# osdelux_proto1_video.net
KiCad netlist of a schematic drawn in EAGLE
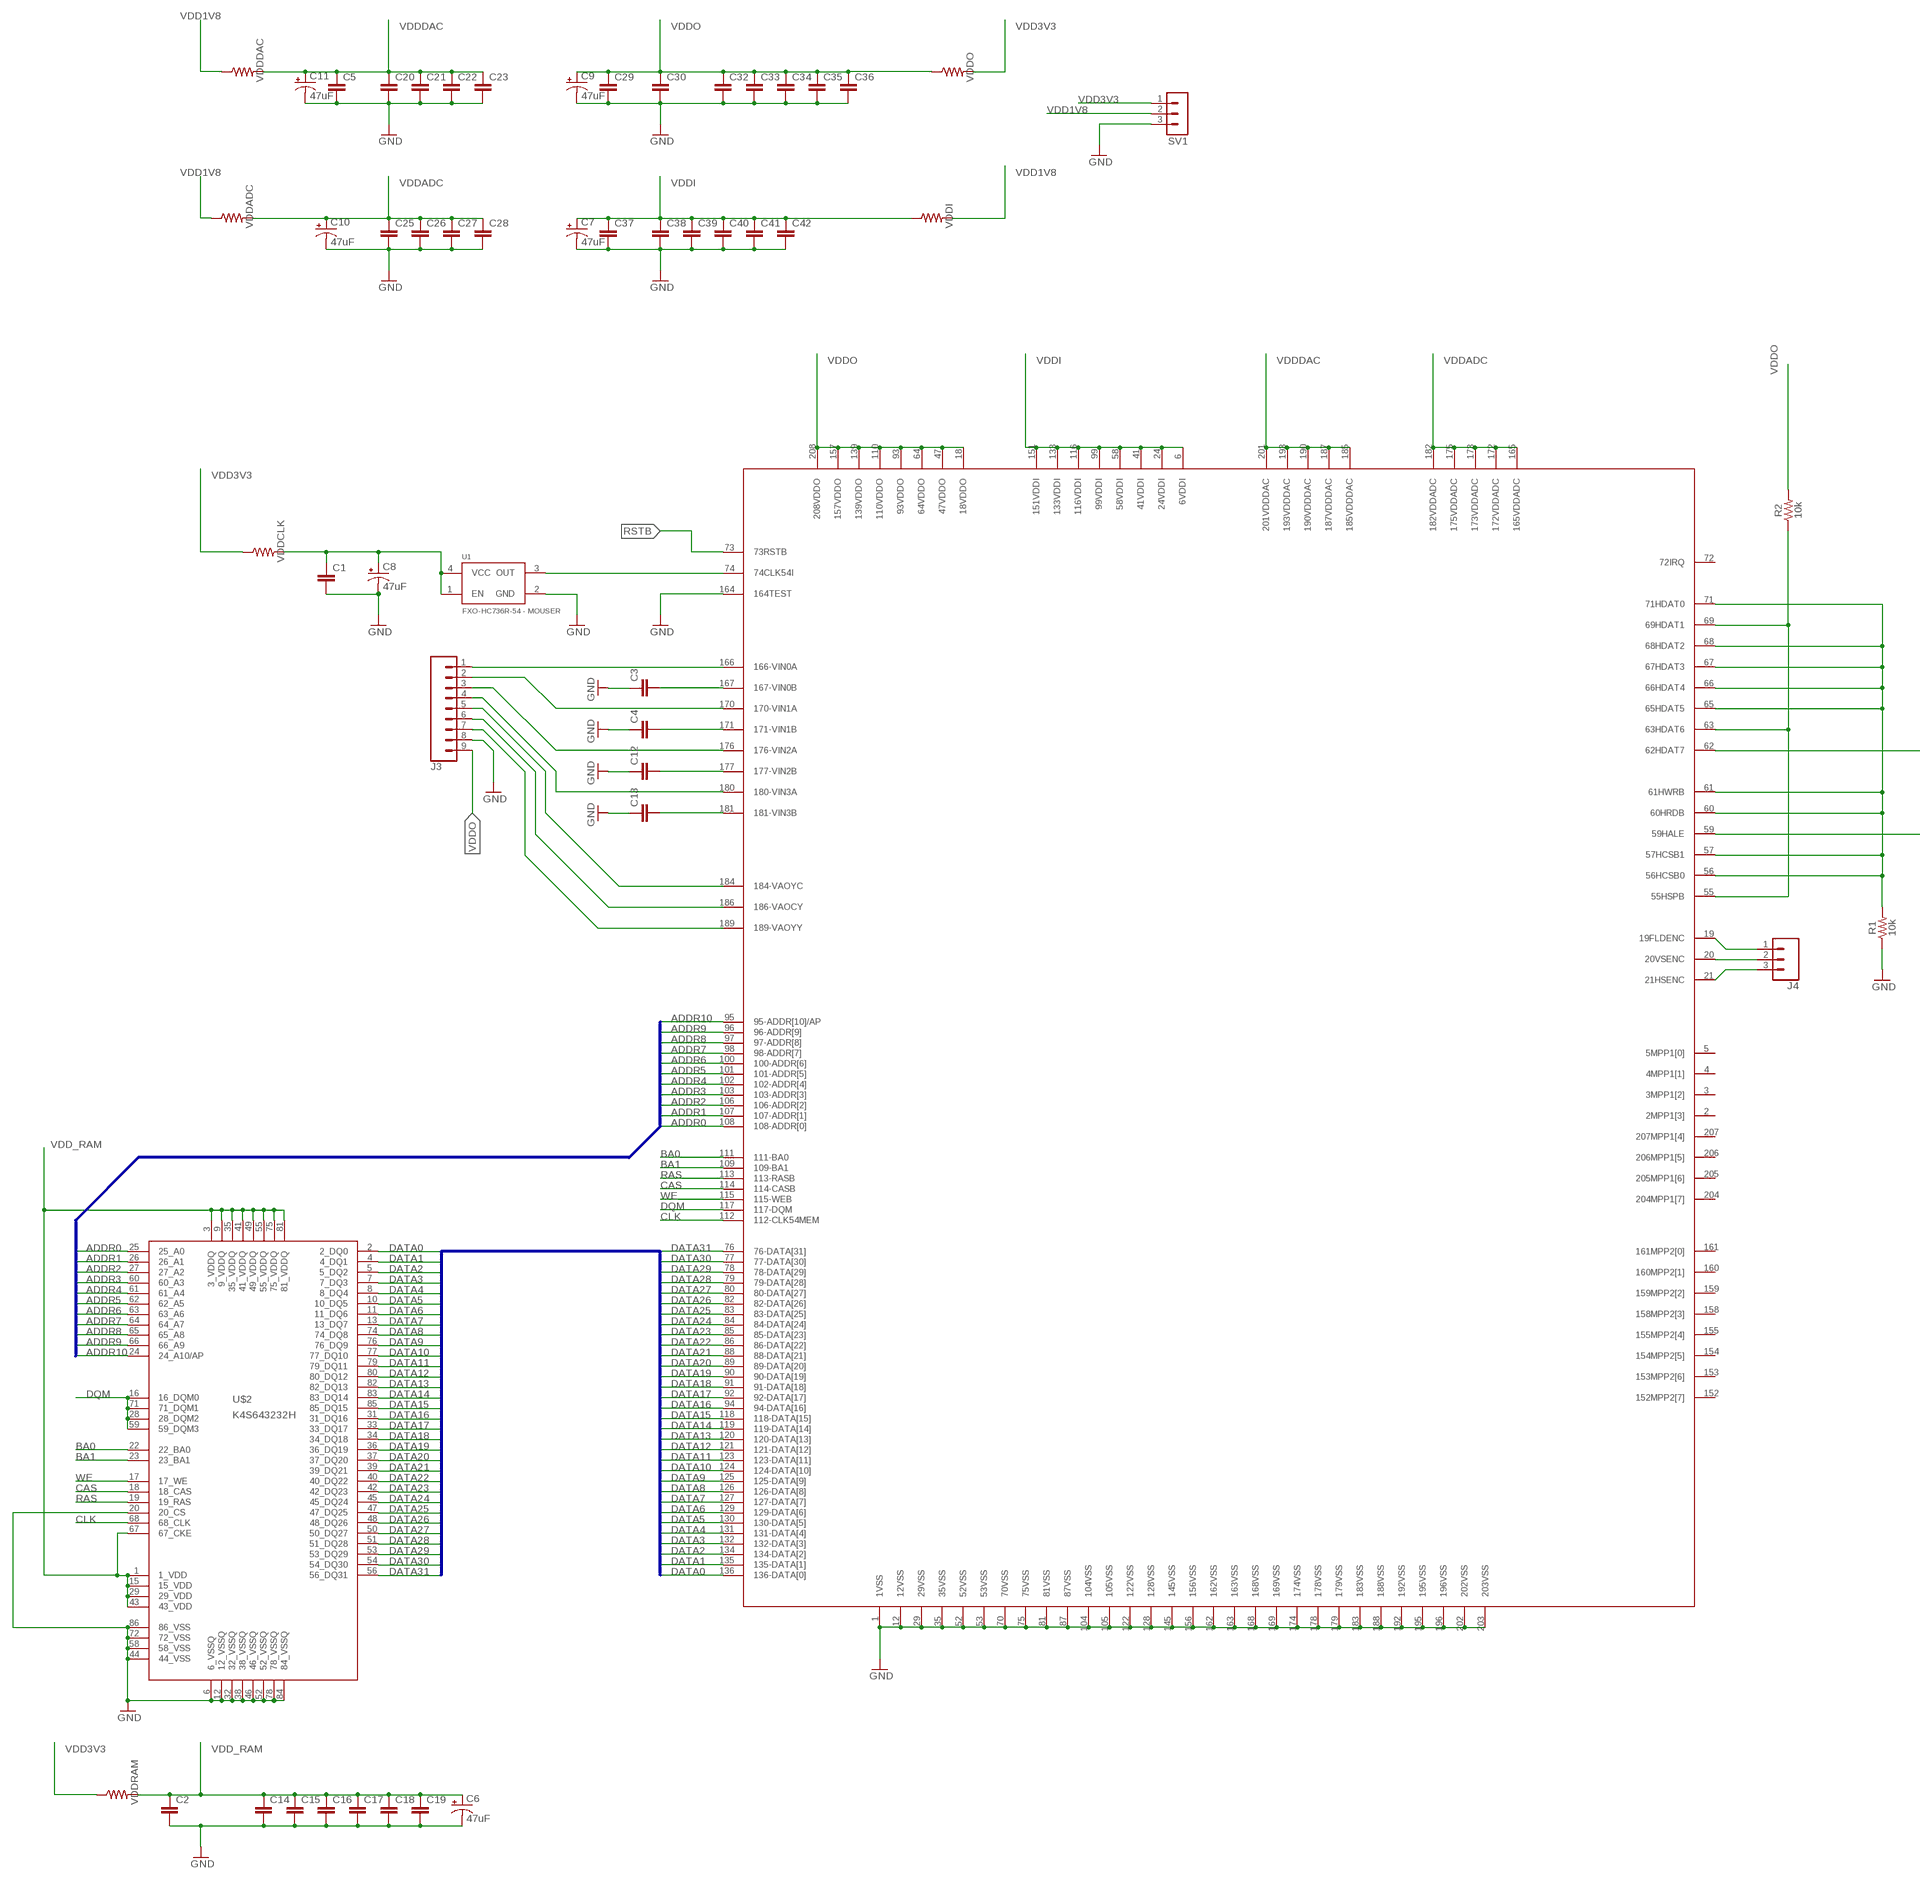
[diagram p0: schematic, sheet 1, part 1 of 2]
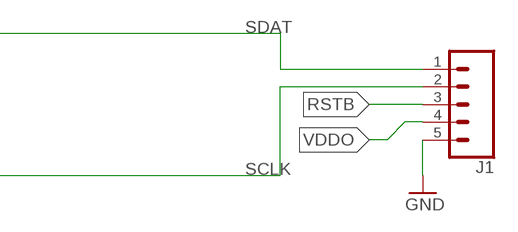
[diagram p1: schematic, sheet 1, part 2 of 2]

(export (version "E")
  (design (tool "Eeschema 10.0.6"))
  (components
    (comp (ref "C1")
      (value "CAP0805")
      (footprint "eagle-import:0805")
      (libsource (lib "eagle-import") (part "CAP0805"))
    )
    (comp (ref "C2")
      (value "CAP0805")
      (footprint "eagle-import:0805")
      (libsource (lib "eagle-import") (part "CAP0805"))
    )
    (comp (ref "C3")
      (value "CAP0805")
      (footprint "eagle-import:0805")
      (libsource (lib "eagle-import") (part "CAP0805"))
    )
    (comp (ref "C4")
      (value "CAP0805")
      (footprint "eagle-import:0805")
      (libsource (lib "eagle-import") (part "CAP0805"))
    )
    (comp (ref "C5")
      (value "CAP0805")
      (footprint "eagle-import:0805")
      (libsource (lib "eagle-import") (part "CAP0805"))
    )
    (comp (ref "C6")
      (value "47uF")
      (footprint "eagle-import:EIA3528")
      (libsource (lib "eagle-import") (part "47UF-POLAR-EIA3528-10V-10%"))
    )
    (comp (ref "C7")
      (value "47uF")
      (footprint "eagle-import:EIA3528")
      (libsource (lib "eagle-import") (part "47UF-POLAR-EIA3528-10V-10%"))
    )
    (comp (ref "C8")
      (value "47uF")
      (footprint "eagle-import:EIA3528")
      (libsource (lib "eagle-import") (part "47UF-POLAR-EIA3528-10V-10%"))
    )
    (comp (ref "C9")
      (value "47uF")
      (footprint "eagle-import:EIA3528")
      (libsource (lib "eagle-import") (part "47UF-POLAR-EIA3528-10V-10%"))
    )
    (comp (ref "C10")
      (value "47uF")
      (footprint "eagle-import:EIA3528")
      (libsource (lib "eagle-import") (part "47UF-POLAR-EIA3528-10V-10%"))
    )
    (comp (ref "C11")
      (value "47uF")
      (footprint "eagle-import:EIA3528")
      (libsource (lib "eagle-import") (part "47UF-POLAR-EIA3528-10V-10%"))
    )
    (comp (ref "C12")
      (value "CAP0805")
      (footprint "eagle-import:0805")
      (libsource (lib "eagle-import") (part "CAP0805"))
    )
    (comp (ref "C13")
      (value "CAP0805")
      (footprint "eagle-import:0805")
      (libsource (lib "eagle-import") (part "CAP0805"))
    )
    (comp (ref "C14")
      (value "CAP0805")
      (footprint "eagle-import:0805")
      (libsource (lib "eagle-import") (part "CAP0805"))
    )
    (comp (ref "C15")
      (value "CAP0805")
      (footprint "eagle-import:0805")
      (libsource (lib "eagle-import") (part "CAP0805"))
    )
    (comp (ref "C16")
      (value "CAP0805")
      (footprint "eagle-import:0805")
      (libsource (lib "eagle-import") (part "CAP0805"))
    )
    (comp (ref "C17")
      (value "CAP0805")
      (footprint "eagle-import:0805")
      (libsource (lib "eagle-import") (part "CAP0805"))
    )
    (comp (ref "C18")
      (value "CAP0805")
      (footprint "eagle-import:0805")
      (libsource (lib "eagle-import") (part "CAP0805"))
    )
    (comp (ref "C19")
      (value "CAP0805")
      (footprint "eagle-import:0805")
      (libsource (lib "eagle-import") (part "CAP0805"))
    )
    (comp (ref "C20")
      (value "CAP0805")
      (footprint "eagle-import:0805")
      (libsource (lib "eagle-import") (part "CAP0805"))
    )
    (comp (ref "C21")
      (value "CAP0805")
      (footprint "eagle-import:0805")
      (libsource (lib "eagle-import") (part "CAP0805"))
    )
    (comp (ref "C22")
      (value "CAP0805")
      (footprint "eagle-import:0805")
      (libsource (lib "eagle-import") (part "CAP0805"))
    )
    (comp (ref "C23")
      (value "CAP0805")
      (footprint "eagle-import:0805")
      (libsource (lib "eagle-import") (part "CAP0805"))
    )
    (comp (ref "C25")
      (value "CAP0805")
      (footprint "eagle-import:0805")
      (libsource (lib "eagle-import") (part "CAP0805"))
    )
    (comp (ref "C26")
      (value "CAP0805")
      (footprint "eagle-import:0805")
      (libsource (lib "eagle-import") (part "CAP0805"))
    )
    (comp (ref "C27")
      (value "CAP0805")
      (footprint "eagle-import:0805")
      (libsource (lib "eagle-import") (part "CAP0805"))
    )
    (comp (ref "C28")
      (value "CAP0805")
      (footprint "eagle-import:0805")
      (libsource (lib "eagle-import") (part "CAP0805"))
    )
    (comp (ref "C29")
      (value "CAP0805")
      (footprint "eagle-import:0805")
      (libsource (lib "eagle-import") (part "CAP0805"))
    )
    (comp (ref "C30")
      (value "CAP0805")
      (footprint "eagle-import:0805")
      (libsource (lib "eagle-import") (part "CAP0805"))
    )
    (comp (ref "C32")
      (value "CAP0805")
      (footprint "eagle-import:0805")
      (libsource (lib "eagle-import") (part "CAP0805"))
    )
    (comp (ref "C33")
      (value "CAP0805")
      (footprint "eagle-import:0805")
      (libsource (lib "eagle-import") (part "CAP0805"))
    )
    (comp (ref "C34")
      (value "CAP0805")
      (footprint "eagle-import:0805")
      (libsource (lib "eagle-import") (part "CAP0805"))
    )
    (comp (ref "C35")
      (value "CAP0805")
      (footprint "eagle-import:0805")
      (libsource (lib "eagle-import") (part "CAP0805"))
    )
    (comp (ref "C36")
      (value "CAP0805")
      (footprint "eagle-import:0805")
      (libsource (lib "eagle-import") (part "CAP0805"))
    )
    (comp (ref "C37")
      (value "CAP0805")
      (footprint "eagle-import:0805")
      (libsource (lib "eagle-import") (part "CAP0805"))
    )
    (comp (ref "C38")
      (value "CAP0805")
      (footprint "eagle-import:0805")
      (libsource (lib "eagle-import") (part "CAP0805"))
    )
    (comp (ref "C39")
      (value "CAP0805")
      (footprint "eagle-import:0805")
      (libsource (lib "eagle-import") (part "CAP0805"))
    )
    (comp (ref "C40")
      (value "CAP0805")
      (footprint "eagle-import:0805")
      (libsource (lib "eagle-import") (part "CAP0805"))
    )
    (comp (ref "C41")
      (value "CAP0805")
      (footprint "eagle-import:0805")
      (libsource (lib "eagle-import") (part "CAP0805"))
    )
    (comp (ref "C42")
      (value "CAP0805")
      (footprint "eagle-import:0805")
      (libsource (lib "eagle-import") (part "CAP0805"))
    )
    (comp (ref "J1")
      (value "CONN_05LOCK_LONGPADS")
      (footprint "eagle-import:1X05_LOCK_LONGPADS")
      (libsource (lib "eagle-import") (part "CONN_05LOCK_LONGPADS"))
    )
    (comp (ref "J3")
      (value "CONN_09LOCK-LONGPADS")
      (footprint "eagle-import:1X09_LOCK_LONGPADS")
      (libsource (lib "eagle-import") (part "CONN_09LOCK-LONGPADS"))
    )
    (comp (ref "J4")
      (value "CONN_03LOCK_LONGPADS")
      (footprint "eagle-import:1X03_LOCK_LONGPADS")
      (libsource (lib "eagle-import") (part "CONN_03LOCK_LONGPADS"))
    )
    (comp (ref "R1")
      (value "10k")
      (footprint "eagle-import:0805")
      (libsource (lib "eagle-import") (part "RESISTOR0805"))
    )
    (comp (ref "R2")
      (value "10k")
      (footprint "eagle-import:0805")
      (libsource (lib "eagle-import") (part "RESISTOR0805"))
    )
    (comp (ref "SV1")
      (value "MA03-1")
      (footprint "eagle-import:MA03-1")
      (libsource (lib "eagle-import") (part "MA03-1"))
    )
    (comp (ref "U$1")
      (value "TW2823")
      (footprint "eagle-import:LQFP208")
      (libsource (lib "eagle-import") (part "TW2823"))
    )
    (comp (ref "U$2")
      (value "K4S643232H")
      (footprint "eagle-import:TSOP86")
      (libsource (lib "eagle-import") (part "K4S643232H"))
    )
    (comp (ref "U1")
      (value "FXO-HC736R-54 - MOUSER")
      (footprint "eagle-import:CRYSTAL-SMD-7.5X5.2-6PIN")
      (libsource (lib "eagle-import") (part "OSCILLATORSMD6"))
    )
    (comp (ref "VDDADC")
      (value "RESISTOR1206")
      (footprint "eagle-import:1206")
      (libsource (lib "eagle-import") (part "RESISTOR1206"))
    )
    (comp (ref "VDDCLK")
      (value "RESISTOR1206")
      (footprint "eagle-import:1206")
      (libsource (lib "eagle-import") (part "RESISTOR1206"))
    )
    (comp (ref "VDDDAC")
      (value "RESISTOR1206")
      (footprint "eagle-import:1206")
      (libsource (lib "eagle-import") (part "RESISTOR1206"))
    )
    (comp (ref "VDDI")
      (value "RESISTOR1206")
      (footprint "eagle-import:1206")
      (libsource (lib "eagle-import") (part "RESISTOR1206"))
    )
    (comp (ref "VDDO")
      (value "RESISTOR1206")
      (footprint "eagle-import:1206")
      (libsource (lib "eagle-import") (part "RESISTOR1206"))
    )
    (comp (ref "VDDRAM")
      (value "RESISTOR1206")
      (footprint "eagle-import:1206")
      (libsource (lib "eagle-import") (part "RESISTOR1206"))
    )
  )
  (nets
    (net (code "1") (name "/72IRQ") (class "Default")
      (node (ref "U$1") (pin "72") (pinfunction "72IRQ_72") (pintype "power_in"))
    )
    (net (code "2") (name "/ADDR0") (class "Default")
      (node (ref "U$1") (pin "108") (pinfunction "108-ADDR[0]_108") (pintype "power_in"))
      (node (ref "U$2") (pin "25") (pinfunction "25_A0_25") (pintype "bidirectional"))
    )
    (net (code "3") (name "/ADDR1") (class "Default")
      (node (ref "U$1") (pin "107") (pinfunction "107-ADDR[1]_107") (pintype "power_in"))
      (node (ref "U$2") (pin "26") (pinfunction "26_A1_26") (pintype "bidirectional"))
    )
    (net (code "4") (name "/ADDR2") (class "Default")
      (node (ref "U$1") (pin "106") (pinfunction "106-ADDR[2]_106") (pintype "power_in"))
      (node (ref "U$2") (pin "27") (pinfunction "27_A2_27") (pintype "bidirectional"))
    )
    (net (code "5") (name "/ADDR3") (class "Default")
      (node (ref "U$1") (pin "103") (pinfunction "103-ADDR[3]_103") (pintype "power_in"))
      (node (ref "U$2") (pin "60") (pinfunction "60_A3_60") (pintype "bidirectional"))
    )
    (net (code "6") (name "/ADDR4") (class "Default")
      (node (ref "U$1") (pin "102") (pinfunction "102-ADDR[4]_102") (pintype "power_in"))
      (node (ref "U$2") (pin "61") (pinfunction "61_A4_61") (pintype "bidirectional"))
    )
    (net (code "7") (name "/ADDR5") (class "Default")
      (node (ref "U$1") (pin "101") (pinfunction "101-ADDR[5]_101") (pintype "power_in"))
      (node (ref "U$2") (pin "62") (pinfunction "62_A5_62") (pintype "bidirectional"))
    )
    (net (code "8") (name "/ADDR6") (class "Default")
      (node (ref "U$1") (pin "100") (pinfunction "100-ADDR[6]_100") (pintype "power_in"))
      (node (ref "U$2") (pin "63") (pinfunction "63_A6_63") (pintype "bidirectional"))
    )
    (net (code "9") (name "/ADDR7") (class "Default")
      (node (ref "U$1") (pin "98") (pinfunction "98-ADDR[7]_98") (pintype "power_in"))
      (node (ref "U$2") (pin "64") (pinfunction "64_A7_64") (pintype "bidirectional"))
    )
    (net (code "10") (name "/ADDR8") (class "Default")
      (node (ref "U$1") (pin "97") (pinfunction "97-ADDR[8]_97") (pintype "power_in"))
      (node (ref "U$2") (pin "65") (pinfunction "65_A8_65") (pintype "bidirectional"))
    )
    (net (code "11") (name "/ADDR9") (class "Default")
      (node (ref "U$1") (pin "96") (pinfunction "96-ADDR[9]_96") (pintype "power_in"))
      (node (ref "U$2") (pin "66") (pinfunction "66_A9_66") (pintype "bidirectional"))
    )
    (net (code "12") (name "/ADDR10") (class "Default")
      (node (ref "U$1") (pin "95") (pinfunction "95-ADDR[10]/AP_95") (pintype "power_in"))
      (node (ref "U$2") (pin "24") (pinfunction "24_A10/AP_24") (pintype "bidirectional"))
    )
    (net (code "13") (name "/BA0") (class "Default")
      (node (ref "U$1") (pin "111") (pinfunction "111-BA0_111") (pintype "power_in"))
      (node (ref "U$2") (pin "22") (pinfunction "22_BA0_22") (pintype "bidirectional"))
    )
    (net (code "14") (name "/BA1") (class "Default")
      (node (ref "U$1") (pin "109") (pinfunction "109-BA1_109") (pintype "power_in"))
      (node (ref "U$2") (pin "23") (pinfunction "23_BA1_23") (pintype "bidirectional"))
    )
    (net (code "15") (name "/CAS") (class "Default")
      (node (ref "U$1") (pin "114") (pinfunction "114-CASB_114") (pintype "power_in"))
      (node (ref "U$2") (pin "18") (pinfunction "18_CAS_18") (pintype "bidirectional"))
    )
    (net (code "16") (name "/CLK") (class "Default")
      (node (ref "U$1") (pin "112") (pinfunction "112-CLK54MEM_112") (pintype "power_in"))
      (node (ref "U$2") (pin "68") (pinfunction "68_CLK_68") (pintype "bidirectional"))
    )
    (net (code "17") (name "/DATA0") (class "Default")
      (node (ref "U$1") (pin "136") (pinfunction "136-DATA[0]_136") (pintype "power_in"))
      (node (ref "U$2") (pin "2") (pinfunction "2_DQ0_2") (pintype "bidirectional"))
    )
    (net (code "18") (name "/DATA1") (class "Default")
      (node (ref "U$1") (pin "135") (pinfunction "135-DATA[1]_135") (pintype "power_in"))
      (node (ref "U$2") (pin "4") (pinfunction "4_DQ1_4") (pintype "bidirectional"))
    )
    (net (code "19") (name "/DATA2") (class "Default")
      (node (ref "U$1") (pin "134") (pinfunction "134-DATA[2]_134") (pintype "power_in"))
      (node (ref "U$2") (pin "5") (pinfunction "5_DQ2_5") (pintype "bidirectional"))
    )
    (net (code "20") (name "/DATA3") (class "Default")
      (node (ref "U$1") (pin "132") (pinfunction "132-DATA[3]_132") (pintype "power_in"))
      (node (ref "U$2") (pin "7") (pinfunction "7_DQ3_7") (pintype "bidirectional"))
    )
    (net (code "21") (name "/DATA4") (class "Default")
      (node (ref "U$1") (pin "131") (pinfunction "131-DATA[4]_131") (pintype "power_in"))
      (node (ref "U$2") (pin "8") (pinfunction "8_DQ4_8") (pintype "bidirectional"))
    )
    (net (code "22") (name "/DATA5") (class "Default")
      (node (ref "U$1") (pin "130") (pinfunction "130-DATA[5]_130") (pintype "power_in"))
      (node (ref "U$2") (pin "10") (pinfunction "10_DQ5_10") (pintype "bidirectional"))
    )
    (net (code "23") (name "/DATA6") (class "Default")
      (node (ref "U$1") (pin "129") (pinfunction "129-DATA[6]_129") (pintype "power_in"))
      (node (ref "U$2") (pin "11") (pinfunction "11_DQ6_11") (pintype "bidirectional"))
    )
    (net (code "24") (name "/DATA7") (class "Default")
      (node (ref "U$1") (pin "127") (pinfunction "127-DATA[7]_127") (pintype "power_in"))
      (node (ref "U$2") (pin "13") (pinfunction "13_DQ7_13") (pintype "bidirectional"))
    )
    (net (code "25") (name "/DATA8") (class "Default")
      (node (ref "U$1") (pin "126") (pinfunction "126-DATA[8]_126") (pintype "power_in"))
      (node (ref "U$2") (pin "74") (pinfunction "74_DQ8_74") (pintype "bidirectional"))
    )
    (net (code "26") (name "/DATA9") (class "Default")
      (node (ref "U$1") (pin "125") (pinfunction "125-DATA[9]_125") (pintype "power_in"))
      (node (ref "U$2") (pin "76") (pinfunction "76_DQ9_76") (pintype "bidirectional"))
    )
    (net (code "27") (name "/DATA10") (class "Default")
      (node (ref "U$1") (pin "124") (pinfunction "124-DATA[10]_124") (pintype "power_in"))
      (node (ref "U$2") (pin "77") (pinfunction "77_DQ10_77") (pintype "bidirectional"))
    )
    (net (code "28") (name "/DATA11") (class "Default")
      (node (ref "U$1") (pin "123") (pinfunction "123-DATA[11]_123") (pintype "power_in"))
      (node (ref "U$2") (pin "79") (pinfunction "79_DQ11_79") (pintype "bidirectional"))
    )
    (net (code "29") (name "/DATA12") (class "Default")
      (node (ref "U$1") (pin "121") (pinfunction "121-DATA[12]_121") (pintype "power_in"))
      (node (ref "U$2") (pin "80") (pinfunction "80_DQ12_80") (pintype "bidirectional"))
    )
    (net (code "30") (name "/DATA13") (class "Default")
      (node (ref "U$1") (pin "120") (pinfunction "120-DATA[13]_120") (pintype "power_in"))
      (node (ref "U$2") (pin "82") (pinfunction "82_DQ13_82") (pintype "bidirectional"))
    )
    (net (code "31") (name "/DATA14") (class "Default")
      (node (ref "U$1") (pin "119") (pinfunction "119-DATA[14]_119") (pintype "power_in"))
      (node (ref "U$2") (pin "83") (pinfunction "83_DQ14_83") (pintype "bidirectional"))
    )
    (net (code "32") (name "/DATA15") (class "Default")
      (node (ref "U$1") (pin "118") (pinfunction "118-DATA[15]_118") (pintype "power_in"))
      (node (ref "U$2") (pin "85") (pinfunction "85_DQ15_85") (pintype "bidirectional"))
    )
    (net (code "33") (name "/DATA16") (class "Default")
      (node (ref "U$1") (pin "94") (pinfunction "94-DATA[16]_94") (pintype "power_in"))
      (node (ref "U$2") (pin "31") (pinfunction "31_DQ16_31") (pintype "bidirectional"))
    )
    (net (code "34") (name "/DATA17") (class "Default")
      (node (ref "U$1") (pin "92") (pinfunction "92-DATA[17]_92") (pintype "power_in"))
      (node (ref "U$2") (pin "33") (pinfunction "33_DQ17_33") (pintype "bidirectional"))
    )
    (net (code "35") (name "/DATA18") (class "Default")
      (node (ref "U$1") (pin "91") (pinfunction "91-DATA[18]_91") (pintype "power_in"))
      (node (ref "U$2") (pin "34") (pinfunction "34_DQ18_34") (pintype "bidirectional"))
    )
    (net (code "36") (name "/DATA19") (class "Default")
      (node (ref "U$1") (pin "90") (pinfunction "90-DATA[19]_90") (pintype "power_in"))
      (node (ref "U$2") (pin "36") (pinfunction "36_DQ19_36") (pintype "bidirectional"))
    )
    (net (code "37") (name "/DATA20") (class "Default")
      (node (ref "U$1") (pin "89") (pinfunction "89-DATA[20]_89") (pintype "power_in"))
      (node (ref "U$2") (pin "37") (pinfunction "37_DQ20_37") (pintype "bidirectional"))
    )
    (net (code "38") (name "/DATA21") (class "Default")
      (node (ref "U$1") (pin "88") (pinfunction "88-DATA[21]_88") (pintype "power_in"))
      (node (ref "U$2") (pin "39") (pinfunction "39_DQ21_39") (pintype "bidirectional"))
    )
    (net (code "39") (name "/DATA22") (class "Default")
      (node (ref "U$1") (pin "86") (pinfunction "86-DATA[22]_86") (pintype "power_in"))
      (node (ref "U$2") (pin "40") (pinfunction "40_DQ22_40") (pintype "bidirectional"))
    )
    (net (code "40") (name "/DATA23") (class "Default")
      (node (ref "U$1") (pin "85") (pinfunction "85-DATA[23]_85") (pintype "power_in"))
      (node (ref "U$2") (pin "42") (pinfunction "42_DQ23_42") (pintype "bidirectional"))
    )
    (net (code "41") (name "/DATA24") (class "Default")
      (node (ref "U$1") (pin "84") (pinfunction "84-DATA[24]_84") (pintype "power_in"))
      (node (ref "U$2") (pin "45") (pinfunction "45_DQ24_45") (pintype "bidirectional"))
    )
    (net (code "42") (name "/DATA25") (class "Default")
      (node (ref "U$1") (pin "83") (pinfunction "83-DATA[25]_83") (pintype "power_in"))
      (node (ref "U$2") (pin "47") (pinfunction "47_DQ25_47") (pintype "bidirectional"))
    )
    (net (code "43") (name "/DATA26") (class "Default")
      (node (ref "U$1") (pin "82") (pinfunction "82-DATA[26]_82") (pintype "power_in"))
      (node (ref "U$2") (pin "48") (pinfunction "48_DQ26_48") (pintype "bidirectional"))
    )
    (net (code "44") (name "/DATA27") (class "Default")
      (node (ref "U$1") (pin "80") (pinfunction "80-DATA[27]_80") (pintype "power_in"))
      (node (ref "U$2") (pin "50") (pinfunction "50_DQ27_50") (pintype "bidirectional"))
    )
    (net (code "45") (name "/DATA28") (class "Default")
      (node (ref "U$1") (pin "79") (pinfunction "79-DATA[28]_79") (pintype "power_in"))
      (node (ref "U$2") (pin "51") (pinfunction "51_DQ28_51") (pintype "bidirectional"))
    )
    (net (code "46") (name "/DATA29") (class "Default")
      (node (ref "U$1") (pin "78") (pinfunction "78-DATA[29]_78") (pintype "power_in"))
      (node (ref "U$2") (pin "53") (pinfunction "53_DQ29_53") (pintype "bidirectional"))
    )
    (net (code "47") (name "/DATA30") (class "Default")
      (node (ref "U$1") (pin "77") (pinfunction "77-DATA[30]_77") (pintype "power_in"))
      (node (ref "U$2") (pin "54") (pinfunction "54_DQ30_54") (pintype "bidirectional"))
    )
    (net (code "48") (name "/DATA31") (class "Default")
      (node (ref "U$1") (pin "76") (pinfunction "76-DATA[31]_76") (pintype "power_in"))
      (node (ref "U$2") (pin "56") (pinfunction "56_DQ31_56") (pintype "bidirectional"))
    )
    (net (code "49") (name "/DQM") (class "Default")
      (node (ref "U$1") (pin "117") (pinfunction "117-DQM_117") (pintype "power_in"))
      (node (ref "U$2") (pin "16") (pinfunction "16_DQM0_16") (pintype "bidirectional"))
      (node (ref "U$2") (pin "28") (pinfunction "28_DQM2_28") (pintype "bidirectional"))
      (node (ref "U$2") (pin "59") (pinfunction "59_DQM3_59") (pintype "bidirectional"))
      (node (ref "U$2") (pin "71") (pinfunction "71_DQM1_71") (pintype "bidirectional"))
    )
    (net (code "50") (name "/RAS") (class "Default")
      (node (ref "U$1") (pin "113") (pinfunction "113-RASB_113") (pintype "power_in"))
      (node (ref "U$2") (pin "19") (pinfunction "19_RAS_19") (pintype "bidirectional"))
    )
    (net (code "51") (name "/SCLK") (class "Default")
      (node (ref "J1") (pin "2") (pinfunction "2_2") (pintype "passive"))
      (node (ref "U$1") (pin "59") (pinfunction "59HALE_59") (pintype "power_in"))
    )
    (net (code "52") (name "/SDAT") (class "Default")
      (node (ref "J1") (pin "1") (pinfunction "1_1") (pintype "passive"))
      (node (ref "U$1") (pin "62") (pinfunction "62HDAT7_62") (pintype "power_in"))
    )
    (net (code "53") (name "/VDD1V8") (class "Default")
      (node (ref "SV1") (pin "2") (pinfunction "2_2") (pintype "passive"))
      (node (ref "VDDADC") (pin "1") (pinfunction "1_1") (pintype "passive"))
      (node (ref "VDDDAC") (pin "1") (pinfunction "1_1") (pintype "passive"))
      (node (ref "VDDI") (pin "2") (pinfunction "2_2") (pintype "passive"))
    )
    (net (code "54") (name "/VDD3V3") (class "Default")
      (node (ref "SV1") (pin "1") (pinfunction "1_1") (pintype "passive"))
      (node (ref "VDDCLK") (pin "1") (pinfunction "1_1") (pintype "passive"))
      (node (ref "VDDO") (pin "2") (pinfunction "2_2") (pintype "passive"))
      (node (ref "VDDRAM") (pin "1") (pinfunction "1_1") (pintype "passive"))
    )
    (net (code "55") (name "/VDDADC") (class "Default")
      (node (ref "C10") (pin "A") (pinfunction "+_A") (pintype "passive"))
      (node (ref "C25") (pin "1") (pinfunction "1_1") (pintype "passive"))
      (node (ref "C26") (pin "1") (pinfunction "1_1") (pintype "passive"))
      (node (ref "C27") (pin "1") (pinfunction "1_1") (pintype "passive"))
      (node (ref "C28") (pin "1") (pinfunction "1_1") (pintype "passive"))
      (node (ref "U$1") (pin "165") (pinfunction "165VDDADC_165") (pintype "power_in"))
      (node (ref "U$1") (pin "172") (pinfunction "172VDDADC_172") (pintype "power_in"))
      (node (ref "U$1") (pin "173") (pinfunction "173VDDADC_173") (pintype "power_in"))
      (node (ref "U$1") (pin "175") (pinfunction "175VDDADC_175") (pintype "power_in"))
      (node (ref "U$1") (pin "182") (pinfunction "182VDDADC_182") (pintype "power_in"))
      (node (ref "VDDADC") (pin "2") (pinfunction "2_2") (pintype "passive"))
    )
    (net (code "56") (name "/VDDDAC") (class "Default")
      (node (ref "C11") (pin "A") (pinfunction "+_A") (pintype "passive"))
      (node (ref "C20") (pin "1") (pinfunction "1_1") (pintype "passive"))
      (node (ref "C21") (pin "1") (pinfunction "1_1") (pintype "passive"))
      (node (ref "C22") (pin "1") (pinfunction "1_1") (pintype "passive"))
      (node (ref "C23") (pin "1") (pinfunction "1_1") (pintype "passive"))
      (node (ref "C5") (pin "1") (pinfunction "1_1") (pintype "passive"))
      (node (ref "U$1") (pin "185") (pinfunction "185VDDDAC_185") (pintype "power_in"))
      (node (ref "U$1") (pin "187") (pinfunction "187VDDDAC_187") (pintype "power_in"))
      (node (ref "U$1") (pin "190") (pinfunction "190VDDDAC_190") (pintype "power_in"))
      (node (ref "U$1") (pin "193") (pinfunction "193VDDDAC_193") (pintype "power_in"))
      (node (ref "U$1") (pin "201") (pinfunction "201VDDDAC_201") (pintype "power_in"))
      (node (ref "VDDDAC") (pin "2") (pinfunction "2_2") (pintype "passive"))
    )
    (net (code "57") (name "/VDDI") (class "Default")
      (node (ref "C37") (pin "1") (pinfunction "1_1") (pintype "passive"))
      (node (ref "C38") (pin "1") (pinfunction "1_1") (pintype "passive"))
      (node (ref "C39") (pin "1") (pinfunction "1_1") (pintype "passive"))
      (node (ref "C40") (pin "1") (pinfunction "1_1") (pintype "passive"))
      (node (ref "C41") (pin "1") (pinfunction "1_1") (pintype "passive"))
      (node (ref "C42") (pin "1") (pinfunction "1_1") (pintype "passive"))
      (node (ref "C7") (pin "A") (pinfunction "+_A") (pintype "passive"))
      (node (ref "U$1") (pin "116") (pinfunction "116VDDI_116") (pintype "power_in"))
      (node (ref "U$1") (pin "133") (pinfunction "133VDDI_133") (pintype "power_in"))
      (node (ref "U$1") (pin "151") (pinfunction "151VDDI_151") (pintype "power_in"))
      (node (ref "U$1") (pin "24") (pinfunction "24VDDI_24") (pintype "power_in"))
      (node (ref "U$1") (pin "41") (pinfunction "41VDDI_41") (pintype "power_in"))
      (node (ref "U$1") (pin "58") (pinfunction "58VDDI_58") (pintype "power_in"))
      (node (ref "U$1") (pin "6") (pinfunction "6VDDI_6") (pintype "power_in"))
      (node (ref "U$1") (pin "99") (pinfunction "99VDDI_99") (pintype "power_in"))
      (node (ref "VDDI") (pin "1") (pinfunction "1_1") (pintype "passive"))
    )
    (net (code "58") (name "/VDD_RAM") (class "Default")
      (node (ref "C14") (pin "1") (pinfunction "1_1") (pintype "passive"))
      (node (ref "C15") (pin "1") (pinfunction "1_1") (pintype "passive"))
      (node (ref "C16") (pin "1") (pinfunction "1_1") (pintype "passive"))
      (node (ref "C17") (pin "1") (pinfunction "1_1") (pintype "passive"))
      (node (ref "C18") (pin "1") (pinfunction "1_1") (pintype "passive"))
      (node (ref "C19") (pin "1") (pinfunction "1_1") (pintype "passive"))
      (node (ref "C2") (pin "1") (pinfunction "1_1") (pintype "passive"))
      (node (ref "C6") (pin "A") (pinfunction "+_A") (pintype "passive"))
      (node (ref "U$2") (pin "1") (pinfunction "1_VDD_1") (pintype "bidirectional"))
      (node (ref "U$2") (pin "15") (pinfunction "15_VDD_15") (pintype "bidirectional"))
      (node (ref "U$2") (pin "29") (pinfunction "29_VDD_29") (pintype "bidirectional"))
      (node (ref "U$2") (pin "3") (pinfunction "3_VDDQ_3") (pintype "bidirectional"))
      (node (ref "U$2") (pin "35") (pinfunction "35_VDDQ_35") (pintype "bidirectional"))
      (node (ref "U$2") (pin "41") (pinfunction "41_VDDQ_41") (pintype "bidirectional"))
      (node (ref "U$2") (pin "43") (pinfunction "43_VDD_43") (pintype "bidirectional"))
      (node (ref "U$2") (pin "49") (pinfunction "49_VDDQ_49") (pintype "bidirectional"))
      (node (ref "U$2") (pin "55") (pinfunction "55_VDDQ_55") (pintype "bidirectional"))
      (node (ref "U$2") (pin "67") (pinfunction "67_CKE_67") (pintype "bidirectional"))
      (node (ref "U$2") (pin "75") (pinfunction "75_VDDQ_75") (pintype "bidirectional"))
      (node (ref "U$2") (pin "81") (pinfunction "81_VDDQ_81") (pintype "bidirectional"))
      (node (ref "U$2") (pin "9") (pinfunction "9_VDDQ_9") (pintype "bidirectional"))
      (node (ref "VDDRAM") (pin "2") (pinfunction "2_2") (pintype "passive"))
    )
    (net (code "59") (name "/WE") (class "Default")
      (node (ref "U$1") (pin "115") (pinfunction "115-WEB_115") (pintype "power_in"))
      (node (ref "U$2") (pin "17") (pinfunction "17_WE_17") (pintype "bidirectional"))
    )
    (net (code "60") (name "GND") (class "Default")
      (node (ref "C1") (pin "2") (pinfunction "2_2") (pintype "passive"))
      (node (ref "C10") (pin "C") (pinfunction "-_C") (pintype "passive"))
      (node (ref "C11") (pin "C") (pinfunction "-_C") (pintype "passive"))
      (node (ref "C12") (pin "1") (pinfunction "1_1") (pintype "passive"))
      (node (ref "C13") (pin "1") (pinfunction "1_1") (pintype "passive"))
      (node (ref "C14") (pin "2") (pinfunction "2_2") (pintype "passive"))
      (node (ref "C15") (pin "2") (pinfunction "2_2") (pintype "passive"))
      (node (ref "C16") (pin "2") (pinfunction "2_2") (pintype "passive"))
      (node (ref "C17") (pin "2") (pinfunction "2_2") (pintype "passive"))
      (node (ref "C18") (pin "2") (pinfunction "2_2") (pintype "passive"))
      (node (ref "C19") (pin "2") (pinfunction "2_2") (pintype "passive"))
      (node (ref "C2") (pin "2") (pinfunction "2_2") (pintype "passive"))
      (node (ref "C20") (pin "2") (pinfunction "2_2") (pintype "passive"))
      (node (ref "C21") (pin "2") (pinfunction "2_2") (pintype "passive"))
      (node (ref "C22") (pin "2") (pinfunction "2_2") (pintype "passive"))
      (node (ref "C23") (pin "2") (pinfunction "2_2") (pintype "passive"))
      (node (ref "C25") (pin "2") (pinfunction "2_2") (pintype "passive"))
      (node (ref "C26") (pin "2") (pinfunction "2_2") (pintype "passive"))
      (node (ref "C27") (pin "2") (pinfunction "2_2") (pintype "passive"))
      (node (ref "C28") (pin "2") (pinfunction "2_2") (pintype "passive"))
      (node (ref "C29") (pin "2") (pinfunction "2_2") (pintype "passive"))
      (node (ref "C3") (pin "1") (pinfunction "1_1") (pintype "passive"))
      (node (ref "C30") (pin "2") (pinfunction "2_2") (pintype "passive"))
      (node (ref "C32") (pin "2") (pinfunction "2_2") (pintype "passive"))
      (node (ref "C33") (pin "2") (pinfunction "2_2") (pintype "passive"))
      (node (ref "C34") (pin "2") (pinfunction "2_2") (pintype "passive"))
      (node (ref "C35") (pin "2") (pinfunction "2_2") (pintype "passive"))
      (node (ref "C36") (pin "2") (pinfunction "2_2") (pintype "passive"))
      (node (ref "C37") (pin "2") (pinfunction "2_2") (pintype "passive"))
      (node (ref "C38") (pin "2") (pinfunction "2_2") (pintype "passive"))
      (node (ref "C39") (pin "2") (pinfunction "2_2") (pintype "passive"))
      (node (ref "C4") (pin "1") (pinfunction "1_1") (pintype "passive"))
      (node (ref "C40") (pin "2") (pinfunction "2_2") (pintype "passive"))
      (node (ref "C41") (pin "2") (pinfunction "2_2") (pintype "passive"))
      (node (ref "C42") (pin "2") (pinfunction "2_2") (pintype "passive"))
      (node (ref "C5") (pin "2") (pinfunction "2_2") (pintype "passive"))
      (node (ref "C6") (pin "C") (pinfunction "-_C") (pintype "passive"))
      (node (ref "C7") (pin "C") (pinfunction "-_C") (pintype "passive"))
      (node (ref "C8") (pin "C") (pinfunction "-_C") (pintype "passive"))
      (node (ref "C9") (pin "C") (pinfunction "-_C") (pintype "passive"))
      (node (ref "J1") (pin "5") (pinfunction "5_5") (pintype "passive"))
      (node (ref "J3") (pin "8") (pinfunction "8_8") (pintype "passive"))
      (node (ref "R1") (pin "1") (pinfunction "1_1") (pintype "passive"))
      (node (ref "SV1") (pin "3") (pinfunction "3_3") (pintype "passive"))
      (node (ref "U$1") (pin "1") (pinfunction "1VSS_1") (pintype "power_in"))
      (node (ref "U$1") (pin "104") (pinfunction "104VSS_104") (pintype "power_in"))
      (node (ref "U$1") (pin "105") (pinfunction "105VSS_105") (pintype "power_in"))
      (node (ref "U$1") (pin "12") (pinfunction "12VSS_12") (pintype "power_in"))
      (node (ref "U$1") (pin "122") (pinfunction "122VSS_122") (pintype "power_in"))
      (node (ref "U$1") (pin "128") (pinfunction "128VSS_128") (pintype "power_in"))
      (node (ref "U$1") (pin "145") (pinfunction "145VSS_145") (pintype "power_in"))
      (node (ref "U$1") (pin "156") (pinfunction "156VSS_156") (pintype "power_in"))
      (node (ref "U$1") (pin "162") (pinfunction "162VSS_162") (pintype "power_in"))
      (node (ref "U$1") (pin "163") (pinfunction "163VSS_163") (pintype "power_in"))
      (node (ref "U$1") (pin "164") (pinfunction "164TEST_164") (pintype "power_in"))
      (node (ref "U$1") (pin "168") (pinfunction "168VSS_168") (pintype "power_in"))
      (node (ref "U$1") (pin "169") (pinfunction "169VSS_169") (pintype "power_in"))
      (node (ref "U$1") (pin "174") (pinfunction "174VSS_174") (pintype "power_in"))
      (node (ref "U$1") (pin "178") (pinfunction "178VSS_178") (pintype "power_in"))
      (node (ref "U$1") (pin "179") (pinfunction "179VSS_179") (pintype "power_in"))
      (node (ref "U$1") (pin "183") (pinfunction "183VSS_183") (pintype "power_in"))
      (node (ref "U$1") (pin "188") (pinfunction "188VSS_188") (pintype "power_in"))
      (node (ref "U$1") (pin "192") (pinfunction "192VSS_192") (pintype "power_in"))
      (node (ref "U$1") (pin "195") (pinfunction "195VSS_195") (pintype "power_in"))
      (node (ref "U$1") (pin "196") (pinfunction "196VSS_196") (pintype "power_in"))
      (node (ref "U$1") (pin "202") (pinfunction "202VSS_202") (pintype "power_in"))
      (node (ref "U$1") (pin "203") (pinfunction "203VSS_203") (pintype "power_in"))
      (node (ref "U$1") (pin "29") (pinfunction "29VSS_29") (pintype "power_in"))
      (node (ref "U$1") (pin "35") (pinfunction "35VSS_35") (pintype "power_in"))
      (node (ref "U$1") (pin "52") (pinfunction "52VSS_52") (pintype "power_in"))
      (node (ref "U$1") (pin "53") (pinfunction "53VSS_53") (pintype "power_in"))
      (node (ref "U$1") (pin "70") (pinfunction "70VSS_70") (pintype "power_in"))
      (node (ref "U$1") (pin "75") (pinfunction "75VSS_75") (pintype "power_in"))
      (node (ref "U$1") (pin "81") (pinfunction "81VSS_81") (pintype "power_in"))
      (node (ref "U$1") (pin "87") (pinfunction "87VSS_87") (pintype "power_in"))
      (node (ref "U$2") (pin "12") (pinfunction "12_VSSQ_12") (pintype "bidirectional"))
      (node (ref "U$2") (pin "20") (pinfunction "20_CS_20") (pintype "bidirectional"))
      (node (ref "U$2") (pin "32") (pinfunction "32_VSSQ_32") (pintype "bidirectional"))
      (node (ref "U$2") (pin "38") (pinfunction "38_VSSQ_38") (pintype "bidirectional"))
      (node (ref "U$2") (pin "44") (pinfunction "44_VSS_44") (pintype "bidirectional"))
      (node (ref "U$2") (pin "46") (pinfunction "46_VSSQ_46") (pintype "bidirectional"))
      (node (ref "U$2") (pin "52") (pinfunction "52_VSSQ_52") (pintype "bidirectional"))
      (node (ref "U$2") (pin "58") (pinfunction "58_VSS_58") (pintype "bidirectional"))
      (node (ref "U$2") (pin "6") (pinfunction "6_VSSQ_6") (pintype "bidirectional"))
      (node (ref "U$2") (pin "72") (pinfunction "72_VSS_72") (pintype "bidirectional"))
      (node (ref "U$2") (pin "78") (pinfunction "78_VSSQ_78") (pintype "bidirectional"))
      (node (ref "U$2") (pin "84") (pinfunction "84_VSSQ_84") (pintype "bidirectional"))
      (node (ref "U$2") (pin "86") (pinfunction "86_VSS_86") (pintype "bidirectional"))
      (node (ref "U1") (pin "2") (pinfunction "GND_2") (pintype "bidirectional"))
    )
    (net (code "61") (name "Net-(C8-+)") (class "Default")
      (node (ref "C1") (pin "1") (pinfunction "1_1") (pintype "passive"))
      (node (ref "C8") (pin "A") (pinfunction "+_A") (pintype "passive"))
      (node (ref "U1") (pin "1") (pinfunction "EN_1") (pintype "bidirectional"))
      (node (ref "U1") (pin "4") (pinfunction "VCC_4") (pintype "bidirectional"))
      (node (ref "VDDCLK") (pin "2") (pinfunction "2_2") (pintype "passive"))
    )
    (net (code "62") (name "Net-(U$1-19FLDENC)") (class "Default")
      (node (ref "J4") (pin "1") (pinfunction "1_1") (pintype "passive"))
      (node (ref "U$1") (pin "19") (pinfunction "19FLDENC_19") (pintype "bidirectional"))
    )
    (net (code "63") (name "Net-(U$1-20VSENC)") (class "Default")
      (node (ref "J4") (pin "2") (pinfunction "2_2") (pintype "passive"))
      (node (ref "U$1") (pin "20") (pinfunction "20VSENC_20") (pintype "bidirectional"))
    )
    (net (code "64") (name "Net-(U$1-21HSENC)") (class "Default")
      (node (ref "J4") (pin "3") (pinfunction "3_3") (pintype "passive"))
      (node (ref "U$1") (pin "21") (pinfunction "21HSENC_21") (pintype "bidirectional"))
    )
    (net (code "65") (name "Net-(U$1-55HSPB)") (class "Default")
      (node (ref "R2") (pin "1") (pinfunction "1_1") (pintype "passive"))
      (node (ref "U$1") (pin "55") (pinfunction "55HSPB_55") (pintype "power_in"))
      (node (ref "U$1") (pin "63") (pinfunction "63HDAT6_63") (pintype "power_in"))
      (node (ref "U$1") (pin "69") (pinfunction "69HDAT1_69") (pintype "power_in"))
    )
    (net (code "66") (name "Net-(U$1-56HCSB0)") (class "Default")
      (node (ref "R1") (pin "2") (pinfunction "2_2") (pintype "passive"))
      (node (ref "U$1") (pin "56") (pinfunction "56HCSB0_56") (pintype "power_in"))
      (node (ref "U$1") (pin "57") (pinfunction "57HCSB1_57") (pintype "power_in"))
      (node (ref "U$1") (pin "60") (pinfunction "60HRDB_60") (pintype "power_in"))
      (node (ref "U$1") (pin "61") (pinfunction "61HWRB_61") (pintype "power_in"))
      (node (ref "U$1") (pin "65") (pinfunction "65HDAT5_65") (pintype "power_in"))
      (node (ref "U$1") (pin "66") (pinfunction "66HDAT4_66") (pintype "power_in"))
      (node (ref "U$1") (pin "67") (pinfunction "67HDAT3_67") (pintype "power_in"))
      (node (ref "U$1") (pin "68") (pinfunction "68HDAT2_68") (pintype "power_in"))
      (node (ref "U$1") (pin "71") (pinfunction "71HDAT0_71") (pintype "power_in"))
    )
    (net (code "67") (name "Net-(U$1-74CLK54I)") (class "Default")
      (node (ref "U$1") (pin "74") (pinfunction "74CLK54I_74") (pintype "power_in"))
      (node (ref "U1") (pin "3") (pinfunction "OUT_3") (pintype "bidirectional"))
    )
    (net (code "68") (name "Net-(U$1-166-VIN0A)") (class "Default")
      (node (ref "J3") (pin "1") (pinfunction "1_1") (pintype "passive"))
      (node (ref "U$1") (pin "166") (pinfunction "166-VIN0A_166") (pintype "power_in"))
    )
    (net (code "69") (name "Net-(U$1-167-VIN0B)") (class "Default")
      (node (ref "C3") (pin "2") (pinfunction "2_2") (pintype "passive"))
      (node (ref "U$1") (pin "167") (pinfunction "167-VIN0B_167") (pintype "power_in"))
    )
    (net (code "70") (name "Net-(U$1-170-VIN1A)") (class "Default")
      (node (ref "J3") (pin "2") (pinfunction "2_2") (pintype "passive"))
      (node (ref "U$1") (pin "170") (pinfunction "170-VIN1A_170") (pintype "power_in"))
    )
    (net (code "71") (name "Net-(U$1-171-VIN1B)") (class "Default")
      (node (ref "C4") (pin "2") (pinfunction "2_2") (pintype "passive"))
      (node (ref "U$1") (pin "171") (pinfunction "171-VIN1B_171") (pintype "power_in"))
    )
    (net (code "72") (name "Net-(U$1-176-VIN2A)") (class "Default")
      (node (ref "J3") (pin "3") (pinfunction "3_3") (pintype "passive"))
      (node (ref "U$1") (pin "176") (pinfunction "176-VIN2A_176") (pintype "power_in"))
    )
    (net (code "73") (name "Net-(U$1-177-VIN2B)") (class "Default")
      (node (ref "C12") (pin "2") (pinfunction "2_2") (pintype "passive"))
      (node (ref "U$1") (pin "177") (pinfunction "177-VIN2B_177") (pintype "power_in"))
    )
    (net (code "74") (name "Net-(U$1-180-VIN3A)") (class "Default")
      (node (ref "J3") (pin "4") (pinfunction "4_4") (pintype "passive"))
      (node (ref "U$1") (pin "180") (pinfunction "180-VIN3A_180") (pintype "power_in"))
    )
    (net (code "75") (name "Net-(U$1-181-VIN3B)") (class "Default")
      (node (ref "C13") (pin "2") (pinfunction "2_2") (pintype "passive"))
      (node (ref "U$1") (pin "181") (pinfunction "181-VIN3B_181") (pintype "power_in"))
    )
    (net (code "76") (name "Net-(U$1-184-VAOYC)") (class "Default")
      (node (ref "J3") (pin "5") (pinfunction "5_5") (pintype "passive"))
      (node (ref "U$1") (pin "184") (pinfunction "184-VAOYC_184") (pintype "power_in"))
    )
    (net (code "77") (name "Net-(U$1-186-VAOCY)") (class "Default")
      (node (ref "J3") (pin "6") (pinfunction "6_6") (pintype "passive"))
      (node (ref "U$1") (pin "186") (pinfunction "186-VAOCY_186") (pintype "power_in"))
    )
    (net (code "78") (name "Net-(U$1-189-VAOYY)") (class "Default")
      (node (ref "J3") (pin "7") (pinfunction "7_7") (pintype "passive"))
      (node (ref "U$1") (pin "189") (pinfunction "189-VAOYY_189") (pintype "power_in"))
    )
    (net (code "79") (name "RSTB") (class "Default")
      (node (ref "J1") (pin "3") (pinfunction "3_3") (pintype "passive"))
      (node (ref "U$1") (pin "73") (pinfunction "73RSTB_73") (pintype "power_in"))
    )
    (net (code "80") (name "VDDO") (class "Default")
      (node (ref "C29") (pin "1") (pinfunction "1_1") (pintype "passive"))
      (node (ref "C30") (pin "1") (pinfunction "1_1") (pintype "passive"))
      (node (ref "C32") (pin "1") (pinfunction "1_1") (pintype "passive"))
      (node (ref "C33") (pin "1") (pinfunction "1_1") (pintype "passive"))
      (node (ref "C34") (pin "1") (pinfunction "1_1") (pintype "passive"))
      (node (ref "C35") (pin "1") (pinfunction "1_1") (pintype "passive"))
      (node (ref "C36") (pin "1") (pinfunction "1_1") (pintype "passive"))
      (node (ref "C9") (pin "A") (pinfunction "+_A") (pintype "passive"))
      (node (ref "J1") (pin "4") (pinfunction "4_4") (pintype "passive"))
      (node (ref "J3") (pin "9") (pinfunction "9_9") (pintype "passive"))
      (node (ref "R2") (pin "2") (pinfunction "2_2") (pintype "passive"))
      (node (ref "U$1") (pin "110") (pinfunction "110VDDO_110") (pintype "power_in"))
      (node (ref "U$1") (pin "139") (pinfunction "139VDDO_139") (pintype "power_in"))
      (node (ref "U$1") (pin "157") (pinfunction "157VDDO_157") (pintype "power_in"))
      (node (ref "U$1") (pin "18") (pinfunction "18VDDO_18") (pintype "power_in"))
      (node (ref "U$1") (pin "208") (pinfunction "208VDDO_208") (pintype "power_in"))
      (node (ref "U$1") (pin "47") (pinfunction "47VDDO_47") (pintype "power_in"))
      (node (ref "U$1") (pin "64") (pinfunction "64VDDO_64") (pintype "power_in"))
      (node (ref "U$1") (pin "93") (pinfunction "93VDDO_93") (pintype "power_in"))
      (node (ref "VDDO") (pin "1") (pinfunction "1_1") (pintype "passive"))
    )
    (net (code "81") (name "unconnected-(U$1-2MPP1[3]-Pad2)") (class "Default")
      (node (ref "U$1") (pin "2") (pinfunction "2MPP1[3]_2") (pintype "bidirectional"))
    )
    (net (code "82") (name "unconnected-(U$1-3MPP1[2]-Pad3)") (class "Default")
      (node (ref "U$1") (pin "3") (pinfunction "3MPP1[2]_3") (pintype "bidirectional"))
    )
    (net (code "83") (name "unconnected-(U$1-4MPP1[1]-Pad4)") (class "Default")
      (node (ref "U$1") (pin "4") (pinfunction "4MPP1[1]_4") (pintype "bidirectional"))
    )
    (net (code "84") (name "unconnected-(U$1-5MPP1[0]-Pad5)") (class "Default")
      (node (ref "U$1") (pin "5") (pinfunction "5MPP1[0]_5") (pintype "bidirectional"))
    )
    (net (code "85") (name "unconnected-(U$1-152MPP2[7]-Pad152)") (class "Default")
      (node (ref "U$1") (pin "152") (pinfunction "152MPP2[7]_152") (pintype "bidirectional"))
    )
    (net (code "86") (name "unconnected-(U$1-153MPP2[6]-Pad153)") (class "Default")
      (node (ref "U$1") (pin "153") (pinfunction "153MPP2[6]_153") (pintype "bidirectional"))
    )
    (net (code "87") (name "unconnected-(U$1-154MPP2[5]-Pad154)") (class "Default")
      (node (ref "U$1") (pin "154") (pinfunction "154MPP2[5]_154") (pintype "bidirectional"))
    )
    (net (code "88") (name "unconnected-(U$1-155MPP2[4]-Pad155)") (class "Default")
      (node (ref "U$1") (pin "155") (pinfunction "155MPP2[4]_155") (pintype "bidirectional"))
    )
    (net (code "89") (name "unconnected-(U$1-158MPP2[3]-Pad158)") (class "Default")
      (node (ref "U$1") (pin "158") (pinfunction "158MPP2[3]_158") (pintype "bidirectional"))
    )
    (net (code "90") (name "unconnected-(U$1-159MPP2[2]-Pad159)") (class "Default")
      (node (ref "U$1") (pin "159") (pinfunction "159MPP2[2]_159") (pintype "bidirectional"))
    )
    (net (code "91") (name "unconnected-(U$1-160MPP2[1]-Pad160)") (class "Default")
      (node (ref "U$1") (pin "160") (pinfunction "160MPP2[1]_160") (pintype "bidirectional"))
    )
    (net (code "92") (name "unconnected-(U$1-161MPP2[0]-Pad161)") (class "Default")
      (node (ref "U$1") (pin "161") (pinfunction "161MPP2[0]_161") (pintype "bidirectional"))
    )
    (net (code "93") (name "unconnected-(U$1-204MPP1[7]-Pad204)") (class "Default")
      (node (ref "U$1") (pin "204") (pinfunction "204MPP1[7]_204") (pintype "bidirectional"))
    )
    (net (code "94") (name "unconnected-(U$1-205MPP1[6]-Pad205)") (class "Default")
      (node (ref "U$1") (pin "205") (pinfunction "205MPP1[6]_205") (pintype "bidirectional"))
    )
    (net (code "95") (name "unconnected-(U$1-206MPP1[5]-Pad206)") (class "Default")
      (node (ref "U$1") (pin "206") (pinfunction "206MPP1[5]_206") (pintype "bidirectional"))
    )
    (net (code "96") (name "unconnected-(U$1-207MPP1[4]-Pad207)") (class "Default")
      (node (ref "U$1") (pin "207") (pinfunction "207MPP1[4]_207") (pintype "bidirectional"))
    )
  )
)
